# PIC32MX_circuit.net
KiCad netlist of a schematic drawn in Altium Designer
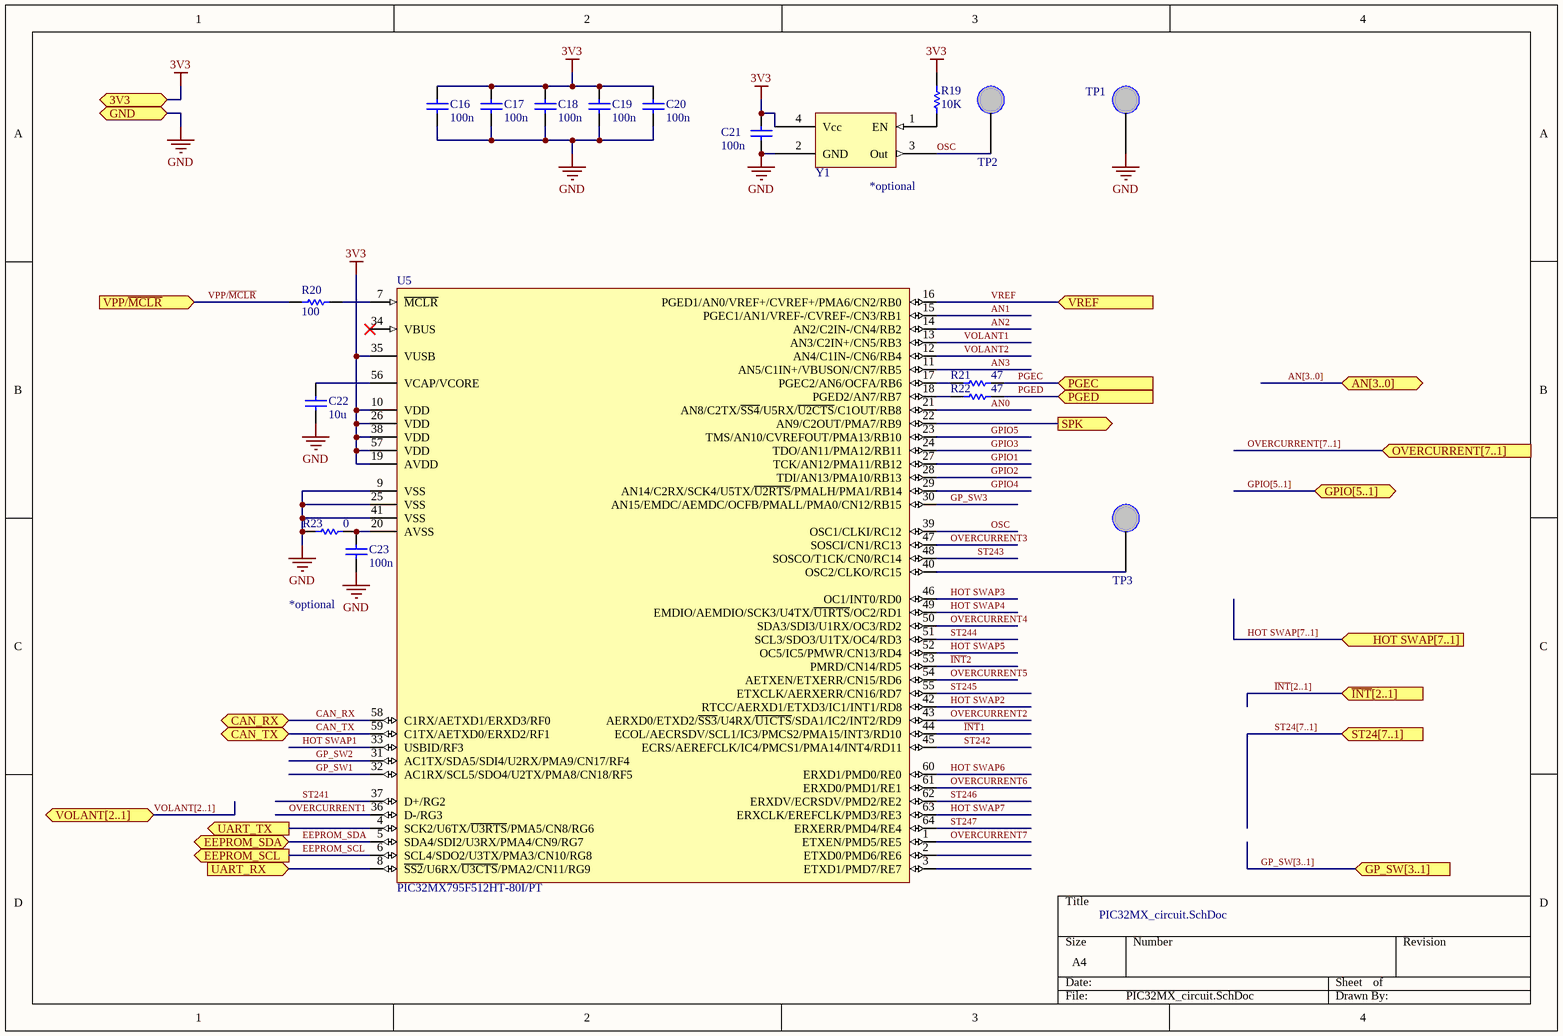
[diagram p0: PIC32MX_circuit.SchDoc]

(export (version "E")
  (design (tool "Eeschema 10.0.6"))
  (components
    (comp (ref "C16")
      (value "100n")
      (footprint "CS-0603")
      (fields
        (field (name "TOLERANCE") "10%")
        (field (name "VOLTAGE") "16V")
        (field (name "Comment") "CS - CAPACITOR")
      )
      (libsource (lib "CHINOOK_LIBRARY") (part "CS - CAPACITOR"))
    )
    (comp (ref "C17")
      (value "100n")
      (footprint "CS-0603")
      (fields
        (field (name "TOLERANCE") "10%")
        (field (name "VOLTAGE") "16V")
        (field (name "Comment") "CS - CAPACITOR")
      )
      (libsource (lib "CHINOOK_LIBRARY") (part "CS - CAPACITOR"))
    )
    (comp (ref "C18")
      (value "100n")
      (footprint "CS-0603")
      (fields
        (field (name "TOLERANCE") "10%")
        (field (name "VOLTAGE") "16V")
        (field (name "Comment") "CS - CAPACITOR")
      )
      (libsource (lib "CHINOOK_LIBRARY") (part "CS - CAPACITOR"))
    )
    (comp (ref "C19")
      (value "100n")
      (footprint "CS-0603")
      (fields
        (field (name "TOLERANCE") "10%")
        (field (name "VOLTAGE") "16V")
        (field (name "Comment") "CS - CAPACITOR")
      )
      (libsource (lib "CHINOOK_LIBRARY") (part "CS - CAPACITOR"))
    )
    (comp (ref "C20")
      (value "100n")
      (footprint "CS-0603")
      (fields
        (field (name "TOLERANCE") "10%")
        (field (name "VOLTAGE") "16V")
        (field (name "Comment") "CS - CAPACITOR")
      )
      (libsource (lib "CHINOOK_LIBRARY") (part "CS - CAPACITOR"))
    )
    (comp (ref "C21")
      (value "100n")
      (footprint "CS-0603")
      (fields
        (field (name "TOLERANCE") "10%")
        (field (name "VOLTAGE") "16V")
        (field (name "Comment") "CS - CAPACITOR")
      )
      (libsource (lib "CHINOOK_LIBRARY") (part "CS - CAPACITOR"))
    )
    (comp (ref "C22")
      (value "10u")
      (footprint "CS-0603")
      (fields
        (field (name "TOLERANCE") "10%")
        (field (name "VOLTAGE") "16V")
        (field (name "Comment") "CS - CAPACITOR")
      )
      (libsource (lib "CHINOOK_LIBRARY") (part "CS - CAPACITOR"))
    )
    (comp (ref "C23")
      (value "100n")
      (footprint "CS-0603")
      (fields
        (field (name "TOLERANCE") "10%")
        (field (name "VOLTAGE") "16V")
        (field (name "Comment") "CS - CAPACITOR")
      )
      (libsource (lib "CHINOOK_LIBRARY") (part "CS - CAPACITOR"))
    )
    (comp (ref "R19")
      (value "10K")
      (footprint "RS-0603")
      (fields
        (field (name "TOLERANCE") "RES TOL")
        (field (name "POWER") "RES POWER")
        (field (name "Comment") "RS - RESISTOR")
      )
      (libsource (lib "CHINOOK_LIBRARY") (part "RS - RESISTOR"))
    )
    (comp (ref "R20")
      (value "100")
      (footprint "RS-0603")
      (fields
        (field (name "TOLERANCE") "RES TOL")
        (field (name "POWER") "RES POWER")
        (field (name "Comment") "RS - RESISTOR")
      )
      (libsource (lib "CHINOOK_LIBRARY") (part "RS - RESISTOR"))
    )
    (comp (ref "R21")
      (value "47")
      (footprint "RS-0603")
      (fields
        (field (name "TOLERANCE") "RES TOL")
        (field (name "POWER") "RES POWER")
        (field (name "Comment") "RS - RESISTOR")
      )
      (libsource (lib "CHINOOK_LIBRARY") (part "RS - RESISTOR"))
    )
    (comp (ref "R22")
      (value "47")
      (footprint "RS-0603")
      (fields
        (field (name "TOLERANCE") "RES TOL")
        (field (name "POWER") "RES POWER")
        (field (name "Comment") "RS - RESISTOR")
      )
      (libsource (lib "CHINOOK_LIBRARY") (part "RS - RESISTOR"))
    )
    (comp (ref "R23")
      (value "0")
      (footprint "RS-0603")
      (fields
        (field (name "TOLERANCE") "RES TOL")
        (field (name "POWER") "RES POWER")
        (field (name "Comment") "RS - RESISTOR")
      )
      (libsource (lib "CHINOOK_LIBRARY") (part "RS - RESISTOR"))
    )
    (comp (ref "TP1")
      (value "5003K")
      (footprint "TP - VERTICAL")
      (libsource (lib "CHINOOK_LIBRARY") (part "TP - Test point vertical"))
    )
    (comp (ref "TP2")
      (value "5003K")
      (footprint "TP - VERTICAL")
      (libsource (lib "CHINOOK_LIBRARY") (part "TP - Test point vertical"))
    )
    (comp (ref "TP3")
      (value "5003K")
      (footprint "TP - VERTICAL")
      (libsource (lib "CHINOOK_LIBRARY") (part "TP - Test point vertical"))
    )
    (comp (ref "U5")
      (value "PIC32MX795F512HT-80I/PT")
      (footprint "IC-TQFP-64")
      (fields (field (name "MANUFACTURER") "Microchip"))
      (libsource (lib "CHINOOK_LIBRARY") (part "IC - PIC32MX795F512HT-80I/PT"))
    )
    (comp (ref "Y1")
      (value "OSC - CB3LV")
      (footprint "OSC-CB3LV")
      (description "Oscillator")
      (libsource (lib "CHINOOK_LIBRARY") (part "OSC - CB3LV"))
    )
  )
  (nets
    (net (code "1") (name "/AN0") (class "Default")
      (node (ref "U5") (pin "21") (pinfunction "AN8/C2TX/~{SS4}/U5RX/~{U2CTS}/C1OUT/RB8_21") (pintype "bidirectional"))
    )
    (net (code "2") (name "/AN1") (class "Default")
      (node (ref "U5") (pin "15") (pinfunction "PGEC1/AN1/VREF-/CVREF-/CN3/RB1_15") (pintype "bidirectional"))
    )
    (net (code "3") (name "/AN2") (class "Default")
      (node (ref "U5") (pin "14") (pinfunction "AN2/C2IN-/CN4/RB2_14") (pintype "bidirectional"))
    )
    (net (code "4") (name "/AN3") (class "Default")
      (node (ref "U5") (pin "11") (pinfunction "AN5/C1IN+/VBUSON/CN7/RB5_11") (pintype "bidirectional"))
    )
    (net (code "6") (name "/CAN_RX") (class "Default")
      (node (ref "U5") (pin "58") (pinfunction "C1RX/AETXD1/ERXD3/RF0_58") (pintype "bidirectional"))
    )
    (net (code "7") (name "/CAN_TX") (class "Default")
      (node (ref "U5") (pin "59") (pinfunction "C1TX/AETXD0/ERXD2/RF1_59") (pintype "bidirectional"))
    )
    (net (code "8") (name "/EEPROM_SCL") (class "Default")
      (node (ref "U5") (pin "6") (pinfunction "SCL4/SDO2/U3TX/PMA3/CN10/RG8_6") (pintype "bidirectional"))
    )
    (net (code "9") (name "/EEPROM_SDA") (class "Default")
      (node (ref "U5") (pin "5") (pinfunction "SDA4/SDI2/U3RX/PMA4/CN9/RG7_5") (pintype "bidirectional"))
    )
    (net (code "10") (name "/GPIO1") (class "Default")
      (node (ref "U5") (pin "27") (pinfunction "TCK/AN12/PMA11/RB12_27") (pintype "bidirectional"))
    )
    (net (code "11") (name "/GPIO2") (class "Default")
      (node (ref "U5") (pin "28") (pinfunction "TDI/AN13/PMA10/RB13_28") (pintype "bidirectional"))
    )
    (net (code "12") (name "/GPIO3") (class "Default")
      (node (ref "U5") (pin "24") (pinfunction "TDO/AN11/PMA12/RB11_24") (pintype "bidirectional"))
    )
    (net (code "13") (name "/GPIO4") (class "Default")
      (node (ref "U5") (pin "29") (pinfunction "AN14/C2RX/SCK4/U5TX/~{U2RTS}/PMALH/PMA1/RB14_29") (pintype "bidirectional"))
    )
    (net (code "14") (name "/GPIO5") (class "Default")
      (node (ref "U5") (pin "23") (pinfunction "TMS/AN10/CVREFOUT/PMA13/RB10_23") (pintype "bidirectional"))
    )
    (net (code "16") (name "/GP_SW1") (class "Default")
      (node (ref "U5") (pin "32") (pinfunction "AC1RX/SCL5/SDO4/U2TX/PMA8/CN18/RF5_32") (pintype "bidirectional"))
    )
    (net (code "17") (name "/GP_SW2") (class "Default")
      (node (ref "U5") (pin "31") (pinfunction "AC1TX/SDA5/SDI4/U2RX/PMA9/CN17/RF4_31") (pintype "bidirectional"))
    )
    (net (code "18") (name "/GP_SW3") (class "Default")
      (node (ref "U5") (pin "30") (pinfunction "AN15/EMDC/AEMDC/OCFB/PMALL/PMA0/CN12/RB15_30") (pintype "bidirectional"))
    )
    (net (code "20") (name "/HOT SWAP1") (class "Default")
      (node (ref "U5") (pin "33") (pinfunction "USBID/RF3_33") (pintype "bidirectional"))
    )
    (net (code "21") (name "/HOT SWAP2") (class "Default")
      (node (ref "U5") (pin "42") (pinfunction "RTCC/AERXD1/ETXD3/IC1/INT1/RD8_42") (pintype "bidirectional"))
    )
    (net (code "22") (name "/HOT SWAP3") (class "Default")
      (node (ref "U5") (pin "46") (pinfunction "OC1/INT0/RD0_46") (pintype "bidirectional"))
    )
    (net (code "23") (name "/HOT SWAP4") (class "Default")
      (node (ref "U5") (pin "49") (pinfunction "EMDIO/AEMDIO/SCK3/U4TX/~{U1RTS}/OC2/RD1_49") (pintype "bidirectional"))
    )
    (net (code "24") (name "/HOT SWAP5") (class "Default")
      (node (ref "U5") (pin "52") (pinfunction "OC5/IC5/PMWR/CN13/RD4_52") (pintype "bidirectional"))
    )
    (net (code "25") (name "/HOT SWAP6") (class "Default")
      (node (ref "U5") (pin "60") (pinfunction "ERXD1/PMD0/RE0_60") (pintype "bidirectional"))
    )
    (net (code "26") (name "/HOT SWAP7") (class "Default")
      (node (ref "U5") (pin "63") (pinfunction "ERXCLK/EREFCLK/PMD3/RE3_63") (pintype "bidirectional"))
    )
    (net (code "27") (name "/OSC") (class "Default")
      (node (ref "TP2") (pin "1") (pinfunction "1_1") (pintype "passive"))
      (node (ref "U5") (pin "39") (pinfunction "OSC1/CLKI/RC12_39") (pintype "bidirectional"))
      (node (ref "Y1") (pin "3") (pinfunction "Out_3") (pintype "output"))
    )
    (net (code "28") (name "/OVERCURRENT1") (class "Default")
      (node (ref "U5") (pin "36") (pinfunction "D-/RG3_36") (pintype "bidirectional"))
    )
    (net (code "29") (name "/OVERCURRENT2") (class "Default")
      (node (ref "U5") (pin "43") (pinfunction "AERXD0/ETXD2/~{SS3}/U4RX/~{U1CTS}/SDA1/IC2/INT2/RD9_43") (pintype "bidirectional"))
    )
    (net (code "30") (name "/OVERCURRENT3") (class "Default")
      (node (ref "U5") (pin "47") (pinfunction "SOSCI/CN1/RC13_47") (pintype "bidirectional"))
    )
    (net (code "31") (name "/OVERCURRENT4") (class "Default")
      (node (ref "U5") (pin "50") (pinfunction "SDA3/SDI3/U1RX/OC3/RD2_50") (pintype "bidirectional"))
    )
    (net (code "32") (name "/OVERCURRENT5") (class "Default")
      (node (ref "U5") (pin "54") (pinfunction "AETXEN/ETXERR/CN15/RD6_54") (pintype "bidirectional"))
    )
    (net (code "33") (name "/OVERCURRENT6") (class "Default")
      (node (ref "U5") (pin "61") (pinfunction "ERXD0/PMD1/RE1_61") (pintype "bidirectional"))
    )
    (net (code "34") (name "/OVERCURRENT7") (class "Default")
      (node (ref "U5") (pin "1") (pinfunction "ETXEN/PMD5/RE5_1") (pintype "bidirectional"))
    )
    (net (code "36") (name "/PGEC") (class "Default")
      (node (ref "R21") (pin "1") (pinfunction "1_1") (pintype "passive"))
    )
    (net (code "37") (name "/PGED") (class "Default")
      (node (ref "R22") (pin "1") (pinfunction "1_1") (pintype "passive"))
    )
    (net (code "38") (name "/SPK") (class "Default")
      (node (ref "U5") (pin "22") (pinfunction "AN9/C2OUT/PMA7/RB9_22") (pintype "bidirectional"))
    )
    (net (code "40") (name "/ST241") (class "Default")
      (node (ref "U5") (pin "37") (pinfunction "D+/RG2_37") (pintype "bidirectional"))
    )
    (net (code "41") (name "/ST242") (class "Default")
      (node (ref "U5") (pin "45") (pinfunction "ECRS/AEREFCLK/IC4/PMCS1/PMA14/INT4/RD11_45") (pintype "bidirectional"))
    )
    (net (code "42") (name "/ST243") (class "Default")
      (node (ref "U5") (pin "48") (pinfunction "SOSCO/T1CK/CN0/RC14_48") (pintype "bidirectional"))
    )
    (net (code "43") (name "/ST244") (class "Default")
      (node (ref "U5") (pin "51") (pinfunction "SCL3/SDO3/U1TX/OC4/RD3_51") (pintype "bidirectional"))
    )
    (net (code "44") (name "/ST245") (class "Default")
      (node (ref "U5") (pin "55") (pinfunction "ETXCLK/AERXERR/CN16/RD7_55") (pintype "bidirectional"))
    )
    (net (code "45") (name "/ST246") (class "Default")
      (node (ref "U5") (pin "62") (pinfunction "ERXDV/ECRSDV/PMD2/RE2_62") (pintype "bidirectional"))
    )
    (net (code "46") (name "/ST247") (class "Default")
      (node (ref "U5") (pin "64") (pinfunction "ERXERR/PMD4/RE4_64") (pintype "bidirectional"))
    )
    (net (code "47") (name "/UART_RX") (class "Default")
      (node (ref "U5") (pin "8") (pinfunction "~{SS2}/U6RX/~{U3CTS}/PMA2/CN11/RG9_8") (pintype "bidirectional"))
    )
    (net (code "48") (name "/UART_TX") (class "Default")
      (node (ref "U5") (pin "4") (pinfunction "SCK2/U6TX/~{U3RTS}/PMA5/CN8/RG6_4") (pintype "bidirectional"))
    )
    (net (code "49") (name "/VOLANT1") (class "Default")
      (node (ref "U5") (pin "13") (pinfunction "AN3/C2IN+/CN5/RB3_13") (pintype "bidirectional"))
    )
    (net (code "50") (name "/VOLANT2") (class "Default")
      (node (ref "U5") (pin "12") (pinfunction "AN4/C1IN-/CN6/RB4_12") (pintype "bidirectional"))
    )
    (net (code "52") (name "/VPP{slash}~{MCLR}") (class "Default")
      (node (ref "R20") (pin "2") (pinfunction "2_2") (pintype "passive"))
    )
    (net (code "53") (name "/VREF") (class "Default")
      (node (ref "U5") (pin "16") (pinfunction "PGED1/AN0/VREF+/CVREF+/PMA6/CN2/RB0_16") (pintype "bidirectional"))
    )
    (net (code "55") (name "/~{INT}1") (class "Default")
      (node (ref "U5") (pin "44") (pinfunction "ECOL/AECRSDV/SCL1/IC3/PMCS2/PMA15/INT3/RD10_44") (pintype "bidirectional"))
    )
    (net (code "56") (name "/~{INT}2") (class "Default")
      (node (ref "U5") (pin "53") (pinfunction "PMRD/CN14/RD5_53") (pintype "bidirectional"))
    )
    (net (code "58") (name "3V3") (class "Default")
      (node (ref "C16") (pin "2") (pinfunction "2_2") (pintype "passive"))
      (node (ref "C17") (pin "2") (pinfunction "2_2") (pintype "passive"))
      (node (ref "C18") (pin "2") (pinfunction "2_2") (pintype "passive"))
      (node (ref "C19") (pin "2") (pinfunction "2_2") (pintype "passive"))
      (node (ref "C20") (pin "2") (pinfunction "2_2") (pintype "passive"))
      (node (ref "C21") (pin "2") (pinfunction "2_2") (pintype "passive"))
      (node (ref "R19") (pin "2") (pinfunction "2_2") (pintype "passive"))
      (node (ref "U5") (pin "10") (pinfunction "VDD_10") (pintype "power_in"))
      (node (ref "U5") (pin "19") (pinfunction "AVDD_19") (pintype "power_in"))
      (node (ref "U5") (pin "26") (pinfunction "VDD_26") (pintype "power_in"))
      (node (ref "U5") (pin "35") (pinfunction "VUSB_35") (pintype "power_in"))
      (node (ref "U5") (pin "38") (pinfunction "VDD_38") (pintype "power_in"))
      (node (ref "U5") (pin "57") (pinfunction "VDD_57") (pintype "power_in"))
      (node (ref "Y1") (pin "4") (pinfunction "Vcc_4") (pintype "power_in"))
    )
    (net (code "59") (name "GND") (class "Default")
      (node (ref "C16") (pin "1") (pinfunction "1_1") (pintype "passive"))
      (node (ref "C17") (pin "1") (pinfunction "1_1") (pintype "passive"))
      (node (ref "C18") (pin "1") (pinfunction "1_1") (pintype "passive"))
      (node (ref "C19") (pin "1") (pinfunction "1_1") (pintype "passive"))
      (node (ref "C20") (pin "1") (pinfunction "1_1") (pintype "passive"))
      (node (ref "C21") (pin "1") (pinfunction "1_1") (pintype "passive"))
      (node (ref "C22") (pin "1") (pinfunction "1_1") (pintype "passive"))
      (node (ref "C23") (pin "1") (pinfunction "1_1") (pintype "passive"))
      (node (ref "R23") (pin "2") (pinfunction "2_2") (pintype "passive"))
      (node (ref "TP1") (pin "1") (pinfunction "1_1") (pintype "passive"))
      (node (ref "U5") (pin "25") (pinfunction "VSS_25") (pintype "power_in"))
      (node (ref "U5") (pin "41") (pinfunction "VSS_41") (pintype "power_in"))
      (node (ref "U5") (pin "9") (pinfunction "VSS_9") (pintype "power_in"))
      (node (ref "Y1") (pin "2") (pinfunction "GND_2") (pintype "power_in"))
    )
    (net (code "60") (name "Net-(U5-AVSS)") (class "Default")
      (node (ref "C23") (pin "2") (pinfunction "2_2") (pintype "passive"))
      (node (ref "R23") (pin "1") (pinfunction "1_1") (pintype "passive"))
      (node (ref "U5") (pin "20") (pinfunction "AVSS_20") (pintype "power_in"))
    )
    (net (code "61") (name "Net-(U5-OSC2{slash}CLKO{slash}RC15)") (class "Default")
      (node (ref "TP3") (pin "1") (pinfunction "1_1") (pintype "passive"))
      (node (ref "U5") (pin "40") (pinfunction "OSC2/CLKO/RC15_40") (pintype "bidirectional"))
    )
    (net (code "62") (name "Net-(U5-PGEC2{slash}AN6{slash}OCFA{slash}RB6)") (class "Default")
      (node (ref "R21") (pin "2") (pinfunction "2_2") (pintype "passive"))
      (node (ref "U5") (pin "17") (pinfunction "PGEC2/AN6/OCFA/RB6_17") (pintype "bidirectional"))
    )
    (net (code "63") (name "Net-(U5-PGED2{slash}AN7{slash}RB7)") (class "Default")
      (node (ref "R22") (pin "2") (pinfunction "2_2") (pintype "passive"))
      (node (ref "U5") (pin "18") (pinfunction "PGED2/AN7/RB7_18") (pintype "bidirectional"))
    )
    (net (code "64") (name "Net-(U5-VCAP{slash}VCORE)") (class "Default")
      (node (ref "C22") (pin "2") (pinfunction "2_2") (pintype "passive"))
      (node (ref "U5") (pin "56") (pinfunction "VCAP/VCORE_56") (pintype "power_in"))
    )
    (net (code "65") (name "Net-(U5-~{MCLR})") (class "Default")
      (node (ref "R20") (pin "1") (pinfunction "1_1") (pintype "passive"))
      (node (ref "U5") (pin "7") (pinfunction "~{MCLR}_7") (pintype "input"))
    )
    (net (code "66") (name "Net-(Y1-EN)") (class "Default")
      (node (ref "R19") (pin "1") (pinfunction "1_1") (pintype "passive"))
      (node (ref "Y1") (pin "1") (pinfunction "EN_1") (pintype "input"))
    )
    (net (code "67") (name "unconnected-(U5-ETXD0{slash}PMD6{slash}RE6-Pad2)") (class "Default")
      (node (ref "U5") (pin "2") (pinfunction "ETXD0/PMD6/RE6_2") (pintype "bidirectional"))
    )
    (net (code "68") (name "unconnected-(U5-ETXD1{slash}PMD7{slash}RE7-Pad3)") (class "Default")
      (node (ref "U5") (pin "3") (pinfunction "ETXD1/PMD7/RE7_3") (pintype "bidirectional"))
    )
    (net (code "69") (name "unconnected-(U5-VBUS-Pad34)") (class "Default")
      (node (ref "U5") (pin "34") (pinfunction "VBUS_34") (pintype "input+no_connect"))
    )
  )
)
